# xboxhdmi.net
KiCad netlist of a schematic drawn in EAGLE
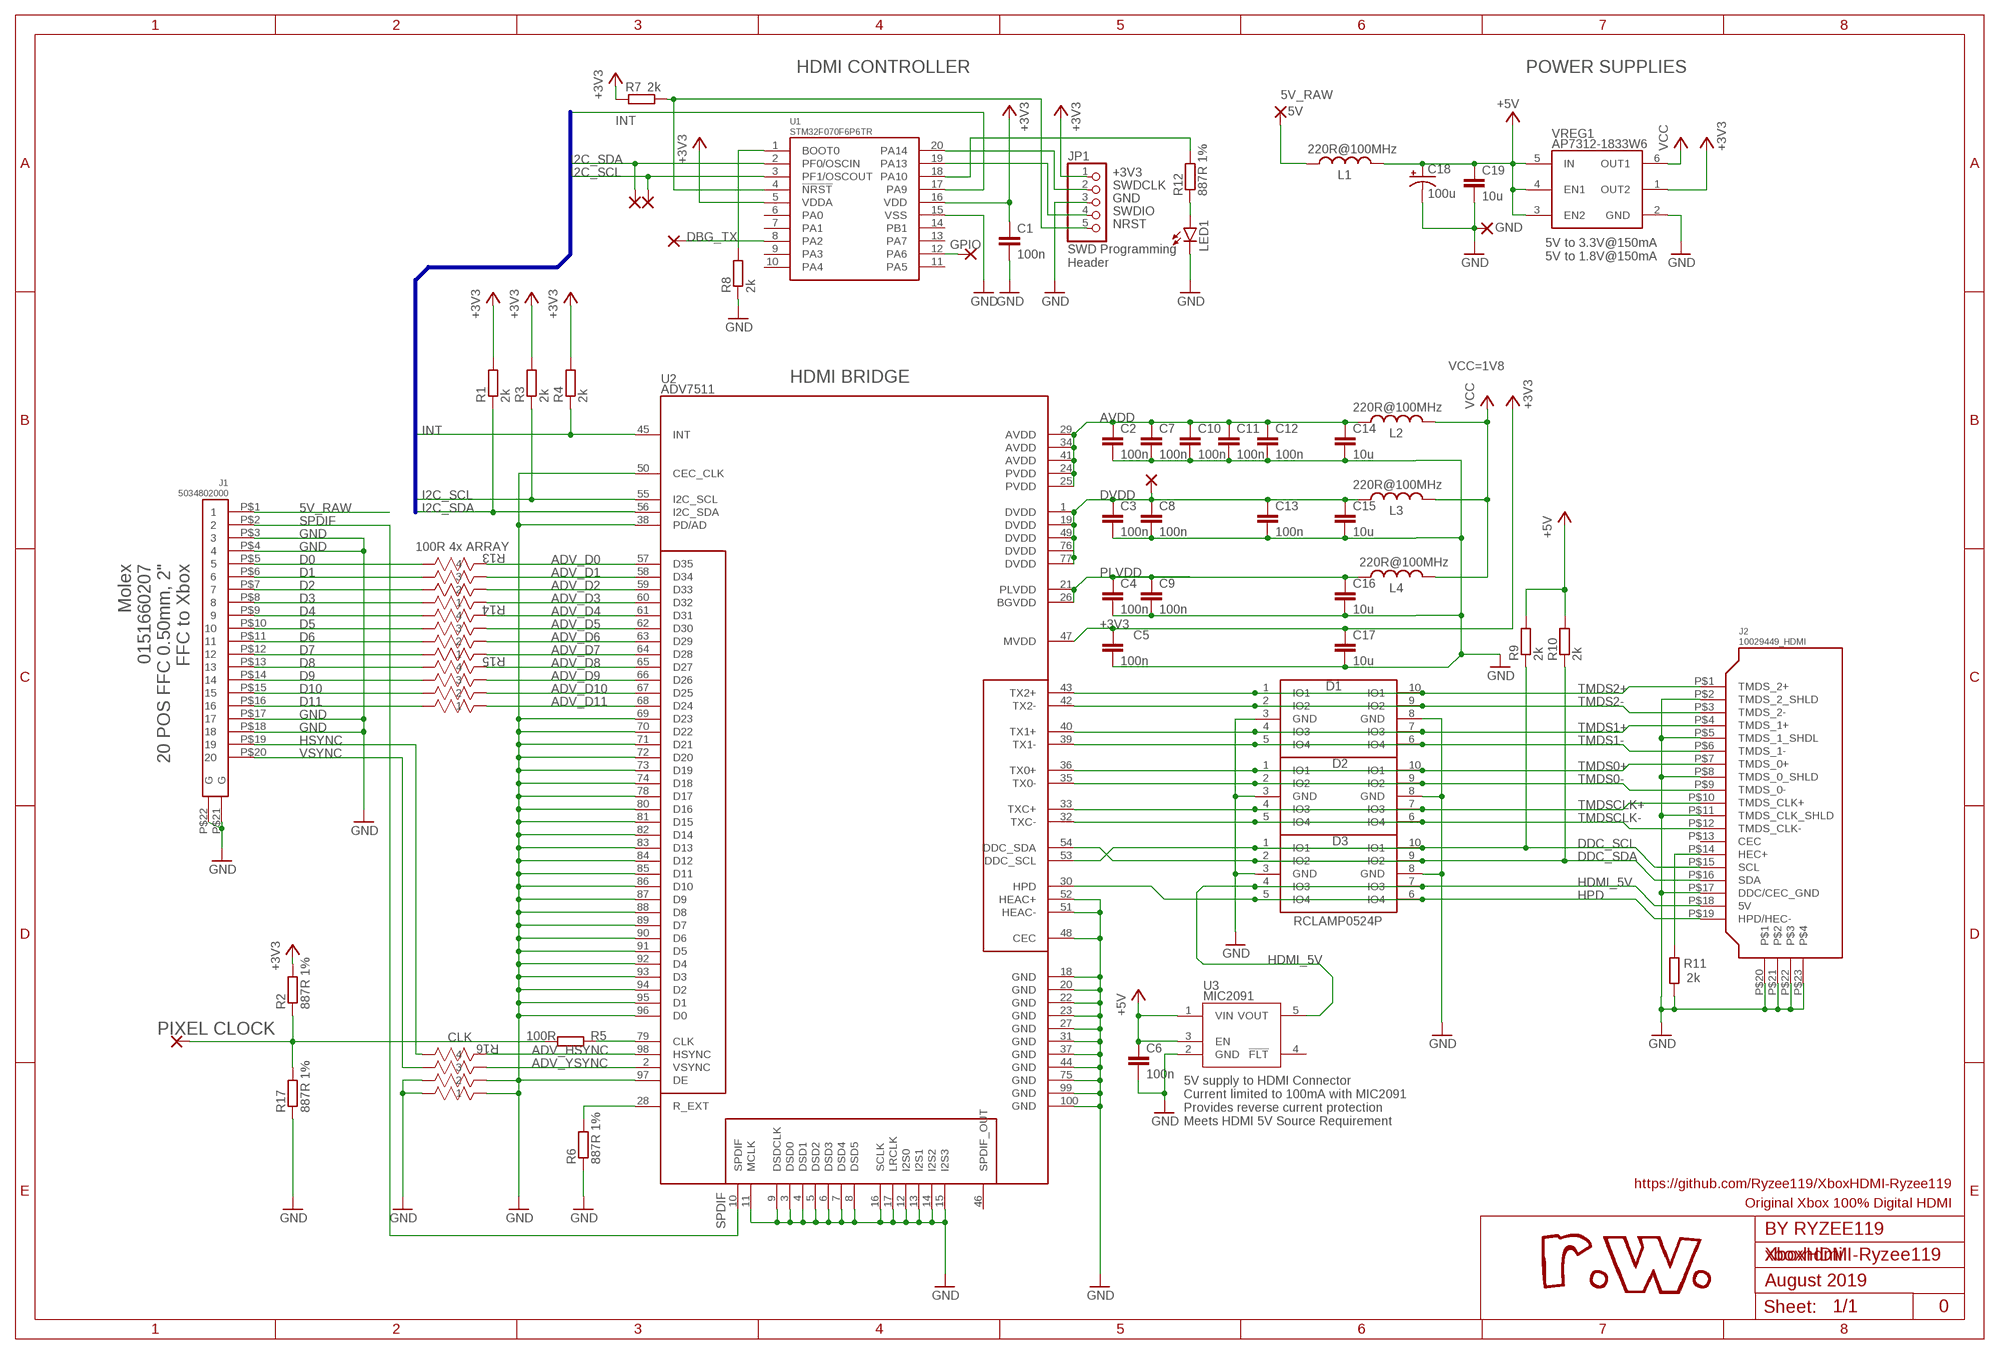
[diagram p0: schematic, sheet 1]

(export (version "E")
  (design (tool "Eeschema 10.0.6"))
  (components
    (comp (ref "1V8")
      (value "SMD2")
      (footprint "eagle-import:SMD1,27-2,54")
      (libsource (lib "eagle-import") (part "SMD2"))
    )
    (comp (ref "5V")
      (value "SMD2")
      (footprint "eagle-import:SMD1,27-2,54")
      (libsource (lib "eagle-import") (part "SMD2"))
    )
    (comp (ref "C1")
      (value "100n")
      (footprint "eagle-import:C0603")
      (libsource (lib "eagle-import") (part "C-EUC0603"))
    )
    (comp (ref "C2")
      (value "100n")
      (footprint "eagle-import:C0603")
      (libsource (lib "eagle-import") (part "C-EUC0603"))
    )
    (comp (ref "C3")
      (value "100n")
      (footprint "eagle-import:C0603")
      (libsource (lib "eagle-import") (part "C-EUC0603"))
    )
    (comp (ref "C4")
      (value "100n")
      (footprint "eagle-import:C0603")
      (libsource (lib "eagle-import") (part "C-EUC0603"))
    )
    (comp (ref "C5")
      (value "100n")
      (footprint "eagle-import:C0603")
      (libsource (lib "eagle-import") (part "C-EUC0603"))
    )
    (comp (ref "C6")
      (value "100n")
      (footprint "eagle-import:C0603")
      (libsource (lib "eagle-import") (part "C-EUC0603"))
    )
    (comp (ref "C7")
      (value "100n")
      (footprint "eagle-import:C0603")
      (libsource (lib "eagle-import") (part "C-EUC0603"))
    )
    (comp (ref "C8")
      (value "100n")
      (footprint "eagle-import:C0603")
      (libsource (lib "eagle-import") (part "C-EUC0603"))
    )
    (comp (ref "C9")
      (value "100n")
      (footprint "eagle-import:C0603")
      (libsource (lib "eagle-import") (part "C-EUC0603"))
    )
    (comp (ref "C10")
      (value "100n")
      (footprint "eagle-import:C0603")
      (libsource (lib "eagle-import") (part "C-EUC0603"))
    )
    (comp (ref "C11")
      (value "100n")
      (footprint "eagle-import:C0603")
      (libsource (lib "eagle-import") (part "C-EUC0603"))
    )
    (comp (ref "C12")
      (value "100n")
      (footprint "eagle-import:C0603")
      (libsource (lib "eagle-import") (part "C-EUC0603"))
    )
    (comp (ref "C13")
      (value "100n")
      (footprint "eagle-import:C0603")
      (libsource (lib "eagle-import") (part "C-EUC0603"))
    )
    (comp (ref "C14")
      (value "10u")
      (footprint "eagle-import:C1206")
      (libsource (lib "eagle-import") (part "C-EUC1206"))
    )
    (comp (ref "C15")
      (value "10u")
      (footprint "eagle-import:C1206")
      (libsource (lib "eagle-import") (part "C-EUC1206"))
    )
    (comp (ref "C16")
      (value "10u")
      (footprint "eagle-import:C1206")
      (libsource (lib "eagle-import") (part "C-EUC1206"))
    )
    (comp (ref "C17")
      (value "10u")
      (footprint "eagle-import:C1206")
      (libsource (lib "eagle-import") (part "C-EUC1206"))
    )
    (comp (ref "C18")
      (value "100u")
      (footprint "eagle-import:153CLV-0505")
      (libsource (lib "eagle-import") (part "CPOL-US153CLV-0505"))
    )
    (comp (ref "C19")
      (value "10u")
      (footprint "eagle-import:C1206")
      (libsource (lib "eagle-import") (part "C-EUC1206"))
    )
    (comp (ref "CLK")
      (value "SMD2")
      (footprint "eagle-import:SMD1,27-2,54")
      (libsource (lib "eagle-import") (part "SMD2"))
    )
    (comp (ref "D1")
      (value "RCLAMP0524P")
      (footprint "eagle-import:DIOCAF50P250X100X65-10")
      (libsource (lib "eagle-import") (part "RCLAMP0524P"))
    )
    (comp (ref "D2")
      (value "RCLAMP0524P")
      (footprint "eagle-import:DIOCAF50P250X100X65-10")
      (libsource (lib "eagle-import") (part "RCLAMP0524P"))
    )
    (comp (ref "D3")
      (value "RCLAMP0524P")
      (footprint "eagle-import:DIOCAF50P250X100X65-10")
      (libsource (lib "eagle-import") (part "RCLAMP0524P"))
    )
    (comp (ref "GND")
      (value "SMD2")
      (footprint "eagle-import:SMD1,27-2,54")
      (libsource (lib "eagle-import") (part "SMD2"))
    )
    (comp (ref "J1")
      (value "5034802000")
      (footprint "eagle-import:5034802000")
      (libsource (lib "eagle-import") (part "5034802000"))
    )
    (comp (ref "J2")
      (value "10029449_HDMI")
      (footprint "eagle-import:HDMI_10029449")
      (libsource (lib "eagle-import") (part "10029449_HDMI"))
    )
    (comp (ref "JP1")
      (value "PINHD-1X5")
      (footprint "eagle-import:1X05")
      (libsource (lib "eagle-import") (part "PINHD-1X5"))
    )
    (comp (ref "L1")
      (value "220R@100MHz")
      (footprint "eagle-import:C0603")
      (libsource (lib "eagle-import") (part "INDUCTOR-0603"))
    )
    (comp (ref "L2")
      (value "220R@100MHz")
      (footprint "eagle-import:C0603")
      (libsource (lib "eagle-import") (part "INDUCTOR-0603"))
    )
    (comp (ref "L3")
      (value "220R@100MHz")
      (footprint "eagle-import:C0603")
      (libsource (lib "eagle-import") (part "INDUCTOR-0603"))
    )
    (comp (ref "L4")
      (value "220R@100MHz")
      (footprint "eagle-import:C0603")
      (libsource (lib "eagle-import") (part "INDUCTOR-0603"))
    )
    (comp (ref "LED1")
      (value "LEDCHIP-LED0603")
      (footprint "eagle-import:CHIP-LED0603")
      (libsource (lib "eagle-import") (part "LEDCHIP-LED0603"))
    )
    (comp (ref "PAD3")
      (value "SMD2")
      (footprint "eagle-import:SMD1,27-2,54")
      (libsource (lib "eagle-import") (part "SMD2"))
    )
    (comp (ref "PAD4")
      (value "SMD2")
      (footprint "eagle-import:SMD1,27-2,54")
      (libsource (lib "eagle-import") (part "SMD2"))
    )
    (comp (ref "PAD5")
      (value "SMD2")
      (footprint "eagle-import:SMD1,27-2,54")
      (libsource (lib "eagle-import") (part "SMD2"))
    )
    (comp (ref "R1")
      (value "2k")
      (footprint "eagle-import:R0603")
      (libsource (lib "eagle-import") (part "R-EU_R0603"))
    )
    (comp (ref "R2")
      (value "887R 1%")
      (footprint "eagle-import:R0603")
      (libsource (lib "eagle-import") (part "R-EU_R0603"))
    )
    (comp (ref "R3")
      (value "2k")
      (footprint "eagle-import:R0603")
      (libsource (lib "eagle-import") (part "R-EU_R0603"))
    )
    (comp (ref "R4")
      (value "2k")
      (footprint "eagle-import:R0603")
      (libsource (lib "eagle-import") (part "R-EU_R0603"))
    )
    (comp (ref "R5")
      (value "100R")
      (footprint "eagle-import:R0603")
      (libsource (lib "eagle-import") (part "R-EU_R0603"))
    )
    (comp (ref "R6")
      (value "887R 1%")
      (footprint "eagle-import:R0603")
      (libsource (lib "eagle-import") (part "R-EU_R0603"))
    )
    (comp (ref "R7")
      (value "2k")
      (footprint "eagle-import:R0603")
      (libsource (lib "eagle-import") (part "R-EU_R0603"))
    )
    (comp (ref "R8")
      (value "2k")
      (footprint "eagle-import:R0603")
      (libsource (lib "eagle-import") (part "R-EU_R0603"))
    )
    (comp (ref "R9")
      (value "2k")
      (footprint "eagle-import:R0603")
      (libsource (lib "eagle-import") (part "R-EU_R0603"))
    )
    (comp (ref "R10")
      (value "2k")
      (footprint "eagle-import:R0603")
      (libsource (lib "eagle-import") (part "R-EU_R0603"))
    )
    (comp (ref "R11")
      (value "2k")
      (footprint "eagle-import:R0603")
      (libsource (lib "eagle-import") (part "R-EU_R0603"))
    )
    (comp (ref "R12")
      (value "887R 1%")
      (footprint "eagle-import:R0603")
      (libsource (lib "eagle-import") (part "R-EU_R0603"))
    )
    (comp (ref "R13")
      (value "YC124-JR-0733RL")
      (footprint "eagle-import:YAG_YC124")
      (fields (field (name "MANUFACTURER_PART_NUMBER") "YC124JR0733RL"))
      (libsource (lib "eagle-import") (part "YC124-JR-0733RL"))
    )
    (comp (ref "R14")
      (value "YC124-JR-0733RL")
      (footprint "eagle-import:YAG_YC124")
      (fields (field (name "MANUFACTURER_PART_NUMBER") "YC124JR0733RL"))
      (libsource (lib "eagle-import") (part "YC124-JR-0733RL"))
    )
    (comp (ref "R15")
      (value "YC124-JR-0733RL")
      (footprint "eagle-import:YAG_YC124")
      (fields (field (name "MANUFACTURER_PART_NUMBER") "YC124JR0733RL"))
      (libsource (lib "eagle-import") (part "YC124-JR-0733RL"))
    )
    (comp (ref "R16")
      (value "YC124-JR-0733RL")
      (footprint "eagle-import:YAG_YC124")
      (fields (field (name "MANUFACTURER_PART_NUMBER") "YC124JR0733RL"))
      (libsource (lib "eagle-import") (part "YC124-JR-0733RL"))
    )
    (comp (ref "R17")
      (value "887R 1%")
      (footprint "eagle-import:R0603")
      (libsource (lib "eagle-import") (part "R-EU_R0603"))
    )
    (comp (ref "TX")
      (value "SMD2")
      (footprint "eagle-import:SMD1,27-2,54")
      (libsource (lib "eagle-import") (part "SMD2"))
    )
    (comp (ref "U1")
      (value "STM32F070F6P6TR")
      (footprint "eagle-import:TSSOP20")
      (libsource (lib "eagle-import") (part "STM32F070F6P6TR"))
    )
    (comp (ref "U2")
      (value "ADV7511")
      (footprint "eagle-import:LQFP100")
      (libsource (lib "eagle-import") (part "ADV7511"))
    )
    (comp (ref "U3")
      (value "MIC2091")
      (footprint "eagle-import:SOT23-5")
      (libsource (lib "eagle-import") (part "MIC2091"))
    )
    (comp (ref "VREG1")
      (value "AP7312-1833W6")
      (footprint "eagle-import:SOT23-6")
      (libsource (lib "eagle-import") (part "AP7312-1833W6"))
    )
  )
  (nets
    (net (code "1") (name "+3V3") (class "Default")
      (node (ref "C1") (pin "1") (pinfunction "1_1") (pintype "passive"))
      (node (ref "C17") (pin "1") (pinfunction "1_1") (pintype "passive"))
      (node (ref "C5") (pin "1") (pinfunction "1_1") (pintype "passive"))
      (node (ref "JP1") (pin "1") (pinfunction "1_1") (pintype "passive"))
      (node (ref "R1") (pin "2") (pinfunction "2_2") (pintype "passive"))
      (node (ref "R2") (pin "2") (pinfunction "2_2") (pintype "passive"))
      (node (ref "R3") (pin "2") (pinfunction "2_2") (pintype "passive"))
      (node (ref "R4") (pin "2") (pinfunction "2_2") (pintype "passive"))
      (node (ref "R7") (pin "2") (pinfunction "2_2") (pintype "passive"))
      (node (ref "U1") (pin "16") (pinfunction "VDD_16") (pintype "bidirectional"))
      (node (ref "U1") (pin "5") (pinfunction "VDDA_5") (pintype "bidirectional"))
      (node (ref "U2") (pin "47") (pinfunction "MVDD_47") (pintype "bidirectional"))
      (node (ref "VREG1") (pin "1") (pinfunction "OUT2_1") (pintype "bidirectional"))
    )
    (net (code "2") (name "+5V") (class "Default")
      (node (ref "C18") (pin "+") (pinfunction "+_+") (pintype "passive"))
      (node (ref "C19") (pin "1") (pinfunction "1_1") (pintype "passive"))
      (node (ref "C6") (pin "1") (pinfunction "1_1") (pintype "passive"))
      (node (ref "L1") (pin "2") (pinfunction "2_2") (pintype "passive"))
      (node (ref "R10") (pin "2") (pinfunction "2_2") (pintype "passive"))
      (node (ref "R9") (pin "2") (pinfunction "2_2") (pintype "passive"))
      (node (ref "U3") (pin "1") (pinfunction "VIN_1") (pintype "bidirectional"))
      (node (ref "U3") (pin "3") (pinfunction "EN_3") (pintype "bidirectional"))
      (node (ref "VREG1") (pin "3") (pinfunction "EN2_3") (pintype "bidirectional"))
      (node (ref "VREG1") (pin "4") (pinfunction "EN1_4") (pintype "bidirectional"))
      (node (ref "VREG1") (pin "5") (pinfunction "IN_5") (pintype "bidirectional"))
    )
    (net (code "3") (name "/5V_RAW") (class "Default")
      (node (ref "5V") (pin "1") (pinfunction "P_1") (pintype "passive"))
      (node (ref "J1") (pin "P$1") (pinfunction "1_P$1") (pintype "bidirectional"))
      (node (ref "L1") (pin "1") (pinfunction "1_1") (pintype "passive"))
    )
    (net (code "4") (name "/ADV_D0") (class "Default")
      (node (ref "R13") (pin "4") (pinfunction "4_4") (pintype "passive"))
      (node (ref "U2") (pin "57") (pinfunction "D35_57") (pintype "bidirectional"))
    )
    (net (code "5") (name "/ADV_D1") (class "Default")
      (node (ref "R13") (pin "3") (pinfunction "3_3") (pintype "passive"))
      (node (ref "U2") (pin "58") (pinfunction "D34_58") (pintype "bidirectional"))
    )
    (net (code "6") (name "/ADV_D2") (class "Default")
      (node (ref "R13") (pin "2") (pinfunction "2_2") (pintype "passive"))
      (node (ref "U2") (pin "59") (pinfunction "D33_59") (pintype "bidirectional"))
    )
    (net (code "7") (name "/ADV_D3") (class "Default")
      (node (ref "R13") (pin "1") (pinfunction "1_1") (pintype "passive"))
      (node (ref "U2") (pin "60") (pinfunction "D32_60") (pintype "bidirectional"))
    )
    (net (code "8") (name "/ADV_D4") (class "Default")
      (node (ref "R14") (pin "4") (pinfunction "4_4") (pintype "passive"))
      (node (ref "U2") (pin "61") (pinfunction "D31_61") (pintype "bidirectional"))
    )
    (net (code "9") (name "/ADV_D5") (class "Default")
      (node (ref "R14") (pin "3") (pinfunction "3_3") (pintype "passive"))
      (node (ref "U2") (pin "62") (pinfunction "D30_62") (pintype "bidirectional"))
    )
    (net (code "10") (name "/ADV_D6") (class "Default")
      (node (ref "R14") (pin "2") (pinfunction "2_2") (pintype "passive"))
      (node (ref "U2") (pin "63") (pinfunction "D29_63") (pintype "bidirectional"))
    )
    (net (code "11") (name "/ADV_D7") (class "Default")
      (node (ref "R14") (pin "1") (pinfunction "1_1") (pintype "passive"))
      (node (ref "U2") (pin "64") (pinfunction "D28_64") (pintype "bidirectional"))
    )
    (net (code "12") (name "/ADV_D8") (class "Default")
      (node (ref "R15") (pin "4") (pinfunction "4_4") (pintype "passive"))
      (node (ref "U2") (pin "65") (pinfunction "D27_65") (pintype "bidirectional"))
    )
    (net (code "13") (name "/ADV_D9") (class "Default")
      (node (ref "R15") (pin "3") (pinfunction "3_3") (pintype "passive"))
      (node (ref "U2") (pin "66") (pinfunction "D26_66") (pintype "bidirectional"))
    )
    (net (code "14") (name "/ADV_D10") (class "Default")
      (node (ref "R15") (pin "2") (pinfunction "2_2") (pintype "passive"))
      (node (ref "U2") (pin "67") (pinfunction "D25_67") (pintype "bidirectional"))
    )
    (net (code "15") (name "/ADV_D11") (class "Default")
      (node (ref "R15") (pin "1") (pinfunction "1_1") (pintype "passive"))
      (node (ref "U2") (pin "68") (pinfunction "D24_68") (pintype "bidirectional"))
    )
    (net (code "16") (name "/ADV_HSYNC") (class "Default")
      (node (ref "R16") (pin "4") (pinfunction "4_4") (pintype "passive"))
      (node (ref "U2") (pin "98") (pinfunction "HSYNC_98") (pintype "bidirectional"))
    )
    (net (code "17") (name "/ADV_YSYNC") (class "Default")
      (node (ref "R16") (pin "3") (pinfunction "3_3") (pintype "passive"))
      (node (ref "U2") (pin "2") (pinfunction "VSYNC_2") (pintype "bidirectional"))
    )
    (net (code "18") (name "/AVDD") (class "Default")
      (node (ref "C10") (pin "1") (pinfunction "1_1") (pintype "passive"))
      (node (ref "C11") (pin "1") (pinfunction "1_1") (pintype "passive"))
      (node (ref "C12") (pin "1") (pinfunction "1_1") (pintype "passive"))
      (node (ref "C14") (pin "1") (pinfunction "1_1") (pintype "passive"))
      (node (ref "C2") (pin "1") (pinfunction "1_1") (pintype "passive"))
      (node (ref "C7") (pin "1") (pinfunction "1_1") (pintype "passive"))
      (node (ref "L2") (pin "1") (pinfunction "1_1") (pintype "passive"))
      (node (ref "U2") (pin "24") (pinfunction "PVDD_24") (pintype "bidirectional"))
      (node (ref "U2") (pin "25") (pinfunction "PVDD_25") (pintype "bidirectional"))
      (node (ref "U2") (pin "29") (pinfunction "AVDD_29") (pintype "bidirectional"))
      (node (ref "U2") (pin "34") (pinfunction "AVDD_34") (pintype "bidirectional"))
      (node (ref "U2") (pin "41") (pinfunction "AVDD_41") (pintype "bidirectional"))
    )
    (net (code "19") (name "/CLK") (class "Default")
      (node (ref "CLK") (pin "1") (pinfunction "P_1") (pintype "passive"))
      (node (ref "R17") (pin "2") (pinfunction "2_2") (pintype "passive"))
      (node (ref "R2") (pin "1") (pinfunction "1_1") (pintype "passive"))
      (node (ref "R5") (pin "2") (pinfunction "2_2") (pintype "passive"))
    )
    (net (code "20") (name "/D0") (class "Default")
      (node (ref "J1") (pin "P$5") (pinfunction "5_P$5") (pintype "bidirectional"))
      (node (ref "R13") (pin "5") (pinfunction "5_5") (pintype "passive"))
    )
    (net (code "21") (name "/D1") (class "Default")
      (node (ref "J1") (pin "P$6") (pinfunction "6_P$6") (pintype "bidirectional"))
      (node (ref "R13") (pin "6") (pinfunction "6_6") (pintype "passive"))
    )
    (net (code "22") (name "/D2") (class "Default")
      (node (ref "J1") (pin "P$7") (pinfunction "7_P$7") (pintype "bidirectional"))
      (node (ref "R13") (pin "7") (pinfunction "7_7") (pintype "passive"))
    )
    (net (code "23") (name "/D3") (class "Default")
      (node (ref "J1") (pin "P$8") (pinfunction "8_P$8") (pintype "bidirectional"))
      (node (ref "R13") (pin "8") (pinfunction "8_8") (pintype "passive"))
    )
    (net (code "24") (name "/D4") (class "Default")
      (node (ref "J1") (pin "P$9") (pinfunction "9_P$9") (pintype "bidirectional"))
      (node (ref "R14") (pin "5") (pinfunction "5_5") (pintype "passive"))
    )
    (net (code "25") (name "/D5") (class "Default")
      (node (ref "J1") (pin "P$10") (pinfunction "10_P$10") (pintype "bidirectional"))
      (node (ref "R14") (pin "6") (pinfunction "6_6") (pintype "passive"))
    )
    (net (code "26") (name "/D6") (class "Default")
      (node (ref "J1") (pin "P$11") (pinfunction "11_P$11") (pintype "bidirectional"))
      (node (ref "R14") (pin "7") (pinfunction "7_7") (pintype "passive"))
    )
    (net (code "27") (name "/D7") (class "Default")
      (node (ref "J1") (pin "P$12") (pinfunction "12_P$12") (pintype "bidirectional"))
      (node (ref "R14") (pin "8") (pinfunction "8_8") (pintype "passive"))
    )
    (net (code "28") (name "/D8") (class "Default")
      (node (ref "J1") (pin "P$13") (pinfunction "13_P$13") (pintype "bidirectional"))
      (node (ref "R15") (pin "5") (pinfunction "5_5") (pintype "passive"))
    )
    (net (code "29") (name "/D9") (class "Default")
      (node (ref "J1") (pin "P$14") (pinfunction "14_P$14") (pintype "bidirectional"))
      (node (ref "R15") (pin "6") (pinfunction "6_6") (pintype "passive"))
    )
    (net (code "30") (name "/D10") (class "Default")
      (node (ref "J1") (pin "P$15") (pinfunction "15_P$15") (pintype "bidirectional"))
      (node (ref "R15") (pin "7") (pinfunction "7_7") (pintype "passive"))
    )
    (net (code "31") (name "/D11") (class "Default")
      (node (ref "J1") (pin "P$16") (pinfunction "16_P$16") (pintype "bidirectional"))
      (node (ref "R15") (pin "8") (pinfunction "8_8") (pintype "passive"))
    )
    (net (code "32") (name "/DBG_TX") (class "Default")
      (node (ref "TX") (pin "1") (pinfunction "P_1") (pintype "passive"))
      (node (ref "U1") (pin "8") (pinfunction "PA2_8") (pintype "bidirectional"))
    )
    (net (code "33") (name "/DDC_SCL") (class "Default")
      (node (ref "D3") (pin "1") (pinfunction "IO1_1") (pintype "bidirectional"))
      (node (ref "D3") (pin "10") (pinfunction "IO1_10") (pintype "bidirectional"))
      (node (ref "J2") (pin "P$15") (pinfunction "SCL_P$15") (pintype "bidirectional"))
      (node (ref "R9") (pin "1") (pinfunction "1_1") (pintype "passive"))
      (node (ref "U2") (pin "53") (pinfunction "DDC_SCL_53") (pintype "bidirectional"))
    )
    (net (code "34") (name "/DDC_SDA") (class "Default")
      (node (ref "D3") (pin "2") (pinfunction "IO2_2") (pintype "bidirectional"))
      (node (ref "D3") (pin "9") (pinfunction "IO2_9") (pintype "bidirectional"))
      (node (ref "J2") (pin "P$16") (pinfunction "SDA_P$16") (pintype "bidirectional"))
      (node (ref "R10") (pin "1") (pinfunction "1_1") (pintype "passive"))
      (node (ref "U2") (pin "54") (pinfunction "DDC_SDA_54") (pintype "bidirectional"))
    )
    (net (code "35") (name "/DVDD") (class "Default")
      (node (ref "1V8") (pin "1") (pinfunction "P_1") (pintype "passive"))
      (node (ref "C13") (pin "1") (pinfunction "1_1") (pintype "passive"))
      (node (ref "C15") (pin "1") (pinfunction "1_1") (pintype "passive"))
      (node (ref "C3") (pin "1") (pinfunction "1_1") (pintype "passive"))
      (node (ref "C8") (pin "1") (pinfunction "1_1") (pintype "passive"))
      (node (ref "L3") (pin "1") (pinfunction "1_1") (pintype "passive"))
      (node (ref "U2") (pin "1") (pinfunction "DVDD_1") (pintype "bidirectional"))
      (node (ref "U2") (pin "19") (pinfunction "DVDD_19") (pintype "bidirectional"))
      (node (ref "U2") (pin "49") (pinfunction "DVDD_49") (pintype "bidirectional"))
      (node (ref "U2") (pin "76") (pinfunction "DVDD_76") (pintype "bidirectional"))
      (node (ref "U2") (pin "77") (pinfunction "DVDD_77") (pintype "bidirectional"))
    )
    (net (code "36") (name "/GPIO") (class "Default")
      (node (ref "PAD5") (pin "1") (pinfunction "P_1") (pintype "passive"))
      (node (ref "U1") (pin "12") (pinfunction "PA6_12") (pintype "bidirectional"))
    )
    (net (code "37") (name "/HDMI_5V") (class "Default")
      (node (ref "D3") (pin "4") (pinfunction "IO3_4") (pintype "bidirectional"))
      (node (ref "D3") (pin "7") (pinfunction "IO3_7") (pintype "bidirectional"))
      (node (ref "J2") (pin "P$18") (pinfunction "5V_P$18") (pintype "bidirectional"))
      (node (ref "U3") (pin "5") (pinfunction "VOUT_5") (pintype "bidirectional"))
    )
    (net (code "38") (name "/HPD") (class "Default")
      (node (ref "D3") (pin "5") (pinfunction "IO4_5") (pintype "bidirectional"))
      (node (ref "D3") (pin "6") (pinfunction "IO4_6") (pintype "bidirectional"))
      (node (ref "J2") (pin "P$19") (pinfunction "HPD/HEC-_P$19") (pintype "bidirectional"))
      (node (ref "U2") (pin "30") (pinfunction "HPD_30") (pintype "bidirectional"))
    )
    (net (code "39") (name "/HSYNC") (class "Default")
      (node (ref "J1") (pin "P$19") (pinfunction "19_P$19") (pintype "bidirectional"))
      (node (ref "R16") (pin "5") (pinfunction "5_5") (pintype "passive"))
    )
    (net (code "40") (name "/I2C_SCL") (class "Default")
      (node (ref "PAD4") (pin "1") (pinfunction "P_1") (pintype "passive"))
      (node (ref "R3") (pin "1") (pinfunction "1_1") (pintype "passive"))
      (node (ref "U1") (pin "3") (pinfunction "PF1/OSCOUT_3") (pintype "bidirectional"))
      (node (ref "U2") (pin "55") (pinfunction "I2C_SCL_55") (pintype "bidirectional"))
    )
    (net (code "41") (name "/I2C_SDA") (class "Default")
      (node (ref "PAD3") (pin "1") (pinfunction "P_1") (pintype "passive"))
      (node (ref "R1") (pin "1") (pinfunction "1_1") (pintype "passive"))
      (node (ref "U1") (pin "2") (pinfunction "PF0/OSCIN_2") (pintype "bidirectional"))
      (node (ref "U2") (pin "56") (pinfunction "I2C_SDA_56") (pintype "bidirectional"))
    )
    (net (code "42") (name "/INT") (class "Default")
      (node (ref "R4") (pin "1") (pinfunction "1_1") (pintype "passive"))
      (node (ref "U1") (pin "17") (pinfunction "PA9_17") (pintype "bidirectional"))
      (node (ref "U2") (pin "45") (pinfunction "INT_45") (pintype "bidirectional"))
    )
    (net (code "43") (name "/NRST") (class "Default")
      (node (ref "JP1") (pin "5") (pinfunction "5_5") (pintype "passive"))
      (node (ref "R7") (pin "1") (pinfunction "1_1") (pintype "passive"))
      (node (ref "U1") (pin "4") (pinfunction "~{NRST}_4") (pintype "bidirectional"))
    )
    (net (code "44") (name "/PLVDD") (class "Default")
      (node (ref "C16") (pin "1") (pinfunction "1_1") (pintype "passive"))
      (node (ref "C4") (pin "1") (pinfunction "1_1") (pintype "passive"))
      (node (ref "C9") (pin "1") (pinfunction "1_1") (pintype "passive"))
      (node (ref "L4") (pin "1") (pinfunction "1_1") (pintype "passive"))
      (node (ref "U2") (pin "21") (pinfunction "PLVDD_21") (pintype "bidirectional"))
      (node (ref "U2") (pin "26") (pinfunction "BGVDD_26") (pintype "bidirectional"))
    )
    (net (code "45") (name "/SPDIF") (class "Default")
      (node (ref "J1") (pin "P$2") (pinfunction "2_P$2") (pintype "bidirectional"))
      (node (ref "U2") (pin "10") (pinfunction "SPDIF_10") (pintype "bidirectional"))
    )
    (net (code "46") (name "/SWDCLK") (class "Default")
      (node (ref "JP1") (pin "2") (pinfunction "2_2") (pintype "passive"))
      (node (ref "U1") (pin "20") (pinfunction "PA14_20") (pintype "bidirectional"))
    )
    (net (code "47") (name "/SWDIO") (class "Default")
      (node (ref "JP1") (pin "4") (pinfunction "4_4") (pintype "passive"))
      (node (ref "U1") (pin "19") (pinfunction "PA13_19") (pintype "bidirectional"))
    )
    (net (code "48") (name "/TMDS0+") (class "Default")
      (node (ref "D2") (pin "1") (pinfunction "IO1_1") (pintype "bidirectional"))
      (node (ref "D2") (pin "10") (pinfunction "IO1_10") (pintype "bidirectional"))
      (node (ref "J2") (pin "P$7") (pinfunction "TMDS_0+_P$7") (pintype "bidirectional"))
      (node (ref "U2") (pin "36") (pinfunction "TX0+_36") (pintype "bidirectional"))
    )
    (net (code "49") (name "/TMDS0-") (class "Default")
      (node (ref "D2") (pin "2") (pinfunction "IO2_2") (pintype "bidirectional"))
      (node (ref "D2") (pin "9") (pinfunction "IO2_9") (pintype "bidirectional"))
      (node (ref "J2") (pin "P$9") (pinfunction "TMDS_0-_P$9") (pintype "bidirectional"))
      (node (ref "U2") (pin "35") (pinfunction "TX0-_35") (pintype "bidirectional"))
    )
    (net (code "50") (name "/TMDS1+") (class "Default")
      (node (ref "D1") (pin "4") (pinfunction "IO3_4") (pintype "bidirectional"))
      (node (ref "D1") (pin "7") (pinfunction "IO3_7") (pintype "bidirectional"))
      (node (ref "J2") (pin "P$4") (pinfunction "TMDS_1+_P$4") (pintype "bidirectional"))
      (node (ref "U2") (pin "40") (pinfunction "TX1+_40") (pintype "bidirectional"))
    )
    (net (code "51") (name "/TMDS1-") (class "Default")
      (node (ref "D1") (pin "5") (pinfunction "IO4_5") (pintype "bidirectional"))
      (node (ref "D1") (pin "6") (pinfunction "IO4_6") (pintype "bidirectional"))
      (node (ref "J2") (pin "P$6") (pinfunction "TMDS_1-_P$6") (pintype "bidirectional"))
      (node (ref "U2") (pin "39") (pinfunction "TX1-_39") (pintype "bidirectional"))
    )
    (net (code "52") (name "/TMDS2+") (class "Default")
      (node (ref "D1") (pin "1") (pinfunction "IO1_1") (pintype "bidirectional"))
      (node (ref "D1") (pin "10") (pinfunction "IO1_10") (pintype "bidirectional"))
      (node (ref "J2") (pin "P$1") (pinfunction "TMDS_2+_P$1") (pintype "bidirectional"))
      (node (ref "U2") (pin "43") (pinfunction "TX2+_43") (pintype "bidirectional"))
    )
    (net (code "53") (name "/TMDS2-") (class "Default")
      (node (ref "D1") (pin "2") (pinfunction "IO2_2") (pintype "bidirectional"))
      (node (ref "D1") (pin "9") (pinfunction "IO2_9") (pintype "bidirectional"))
      (node (ref "J2") (pin "P$3") (pinfunction "TMDS_2-_P$3") (pintype "bidirectional"))
      (node (ref "U2") (pin "42") (pinfunction "TX2-_42") (pintype "bidirectional"))
    )
    (net (code "54") (name "/TMDSCLK+") (class "Default")
      (node (ref "D2") (pin "4") (pinfunction "IO3_4") (pintype "bidirectional"))
      (node (ref "D2") (pin "7") (pinfunction "IO3_7") (pintype "bidirectional"))
      (node (ref "J2") (pin "P$10") (pinfunction "TMDS_CLK+_P$10") (pintype "bidirectional"))
      (node (ref "U2") (pin "33") (pinfunction "TXC+_33") (pintype "bidirectional"))
    )
    (net (code "55") (name "/TMDSCLK-") (class "Default")
      (node (ref "D2") (pin "5") (pinfunction "IO4_5") (pintype "bidirectional"))
      (node (ref "D2") (pin "6") (pinfunction "IO4_6") (pintype "bidirectional"))
      (node (ref "J2") (pin "P$12") (pinfunction "TMDS_CLK-_P$12") (pintype "bidirectional"))
      (node (ref "U2") (pin "32") (pinfunction "TXC-_32") (pintype "bidirectional"))
    )
    (net (code "56") (name "/VSYNC") (class "Default")
      (node (ref "J1") (pin "P$20") (pinfunction "20_P$20") (pintype "bidirectional"))
      (node (ref "R16") (pin "6") (pinfunction "6_6") (pintype "passive"))
    )
    (net (code "57") (name "GND") (class "Default")
      (node (ref "C1") (pin "2") (pinfunction "2_2") (pintype "passive"))
      (node (ref "C10") (pin "2") (pinfunction "2_2") (pintype "passive"))
      (node (ref "C11") (pin "2") (pinfunction "2_2") (pintype "passive"))
      (node (ref "C12") (pin "2") (pinfunction "2_2") (pintype "passive"))
      (node (ref "C13") (pin "2") (pinfunction "2_2") (pintype "passive"))
      (node (ref "C14") (pin "2") (pinfunction "2_2") (pintype "passive"))
      (node (ref "C15") (pin "2") (pinfunction "2_2") (pintype "passive"))
      (node (ref "C16") (pin "2") (pinfunction "2_2") (pintype "passive"))
      (node (ref "C17") (pin "2") (pinfunction "2_2") (pintype "passive"))
      (node (ref "C18") (pin "-") (pinfunction "-_-") (pintype "passive"))
      (node (ref "C19") (pin "2") (pinfunction "2_2") (pintype "passive"))
      (node (ref "C2") (pin "2") (pinfunction "2_2") (pintype "passive"))
      (node (ref "C3") (pin "2") (pinfunction "2_2") (pintype "passive"))
      (node (ref "C4") (pin "2") (pinfunction "2_2") (pintype "passive"))
      (node (ref "C5") (pin "2") (pinfunction "2_2") (pintype "passive"))
      (node (ref "C6") (pin "2") (pinfunction "2_2") (pintype "passive"))
      (node (ref "C7") (pin "2") (pinfunction "2_2") (pintype "passive"))
      (node (ref "C8") (pin "2") (pinfunction "2_2") (pintype "passive"))
      (node (ref "C9") (pin "2") (pinfunction "2_2") (pintype "passive"))
      (node (ref "D1") (pin "3") (pinfunction "GND_3") (pintype "bidirectional"))
      (node (ref "D1") (pin "8") (pinfunction "GND_8") (pintype "bidirectional"))
      (node (ref "D2") (pin "3") (pinfunction "GND_3") (pintype "bidirectional"))
      (node (ref "D2") (pin "8") (pinfunction "GND_8") (pintype "bidirectional"))
      (node (ref "D3") (pin "3") (pinfunction "GND_3") (pintype "bidirectional"))
      (node (ref "D3") (pin "8") (pinfunction "GND_8") (pintype "bidirectional"))
      (node (ref "GND") (pin "1") (pinfunction "P_1") (pintype "passive"))
      (node (ref "J1") (pin "P$17") (pinfunction "17_P$17") (pintype "bidirectional"))
      (node (ref "J1") (pin "P$18") (pinfunction "18_P$18") (pintype "bidirectional"))
      (node (ref "J1") (pin "P$21") (pinfunction "G_P$21") (pintype "bidirectional"))
      (node (ref "J1") (pin "P$22") (pinfunction "G_P$22") (pintype "bidirectional"))
      (node (ref "J1") (pin "P$3") (pinfunction "3_P$3") (pintype "bidirectional"))
      (node (ref "J1") (pin "P$4") (pinfunction "4_P$4") (pintype "bidirectional"))
      (node (ref "J2") (pin "P$11") (pinfunction "TMDS_CLK_SHLD_P$11") (pintype "bidirectional"))
      (node (ref "J2") (pin "P$17") (pinfunction "DDC/CEC_GND_P$17") (pintype "bidirectional"))
      (node (ref "J2") (pin "P$2") (pinfunction "TMDS_2_SHLD_P$2") (pintype "bidirectional"))
      (node (ref "J2") (pin "P$20") (pinfunction "P$1_P$20") (pintype "bidirectional"))
      (node (ref "J2") (pin "P$21") (pinfunction "P$2_P$21") (pintype "bidirectional"))
      (node (ref "J2") (pin "P$22") (pinfunction "P$3_P$22") (pintype "bidirectional"))
      (node (ref "J2") (pin "P$23") (pinfunction "P$4_P$23") (pintype "bidirectional"))
      (node (ref "J2") (pin "P$5") (pinfunction "TMDS_1_SHDL_P$5") (pintype "bidirectional"))
      (node (ref "J2") (pin "P$8") (pinfunction "TMDS_0_SHLD_P$8") (pintype "bidirectional"))
      (node (ref "JP1") (pin "3") (pinfunction "3_3") (pintype "passive"))
      (node (ref "LED1") (pin "C") (pinfunction "C_C") (pintype "passive"))
      (node (ref "R11") (pin "1") (pinfunction "1_1") (pintype "passive"))
      (node (ref "R16") (pin "1") (pinfunction "1_1") (pintype "passive"))
      (node (ref "R16") (pin "2") (pinfunction "2_2") (pintype "passive"))
      (node (ref "R16") (pin "7") (pinfunction "7_7") (pintype "passive"))
      (node (ref "R16") (pin "8") (pinfunction "8_8") (pintype "passive"))
      (node (ref "R17") (pin "1") (pinfunction "1_1") (pintype "passive"))
      (node (ref "R6") (pin "1") (pinfunction "1_1") (pintype "passive"))
      (node (ref "R8") (pin "1") (pinfunction "1_1") (pintype "passive"))
      (node (ref "U1") (pin "15") (pinfunction "VSS_15") (pintype "bidirectional"))
      (node (ref "U2") (pin "100") (pinfunction "GND_100") (pintype "bidirectional"))
      (node (ref "U2") (pin "11") (pinfunction "MCLK_11") (pintype "bidirectional"))
      (node (ref "U2") (pin "12") (pinfunction "I2S0_12") (pintype "bidirectional"))
      (node (ref "U2") (pin "13") (pinfunction "I2S1_13") (pintype "bidirectional"))
      (node (ref "U2") (pin "14") (pinfunction "I2S2_14") (pintype "bidirectional"))
      (node (ref "U2") (pin "15") (pinfunction "I2S3_15") (pintype "bidirectional"))
      (node (ref "U2") (pin "16") (pinfunction "SCLK_16") (pintype "bidirectional"))
      (node (ref "U2") (pin "17") (pinfunction "LRCLK_17") (pintype "bidirectional"))
      (node (ref "U2") (pin "18") (pinfunction "GND_18") (pintype "bidirectional"))
      (node (ref "U2") (pin "20") (pinfunction "GND_20") (pintype "bidirectional"))
      (node (ref "U2") (pin "22") (pinfunction "GND_22") (pintype "bidirectional"))
      (node (ref "U2") (pin "23") (pinfunction "GND_23") (pintype "bidirectional"))
      (node (ref "U2") (pin "27") (pinfunction "GND_27") (pintype "bidirectional"))
      (node (ref "U2") (pin "3") (pinfunction "DSD0_3") (pintype "bidirectional"))
      (node (ref "U2") (pin "31") (pinfunction "GND_31") (pintype "bidirectional"))
      (node (ref "U2") (pin "37") (pinfunction "GND_37") (pintype "bidirectional"))
      (node (ref "U2") (pin "38") (pinfunction "PD/AD_38") (pintype "bidirectional"))
      (node (ref "U2") (pin "4") (pinfunction "DSD1_4") (pintype "bidirectional"))
      (node (ref "U2") (pin "44") (pinfunction "GND_44") (pintype "bidirectional"))
      (node (ref "U2") (pin "48") (pinfunction "CEC_48") (pintype "bidirectional"))
      (node (ref "U2") (pin "5") (pinfunction "DSD2_5") (pintype "bidirectional"))
      (node (ref "U2") (pin "50") (pinfunction "CEC_CLK_50") (pintype "bidirectional"))
      (node (ref "U2") (pin "51") (pinfunction "HEAC-_51") (pintype "bidirectional"))
      (node (ref "U2") (pin "52") (pinfunction "HEAC+_52") (pintype "bidirectional"))
      (node (ref "U2") (pin "6") (pinfunction "DSD3_6") (pintype "bidirectional"))
      (node (ref "U2") (pin "69") (pinfunction "D23_69") (pintype "bidirectional"))
      (node (ref "U2") (pin "7") (pinfunction "DSD4_7") (pintype "bidirectional"))
      (node (ref "U2") (pin "70") (pinfunction "D22_70") (pintype "bidirectional"))
      (node (ref "U2") (pin "71") (pinfunction "D21_71") (pintype "bidirectional"))
      (node (ref "U2") (pin "72") (pinfunction "D20_72") (pintype "bidirectional"))
      (node (ref "U2") (pin "73") (pinfunction "D19_73") (pintype "bidirectional"))
      (node (ref "U2") (pin "74") (pinfunction "D18_74") (pintype "bidirectional"))
      (node (ref "U2") (pin "75") (pinfunction "GND_75") (pintype "bidirectional"))
      (node (ref "U2") (pin "78") (pinfunction "D17_78") (pintype "bidirectional"))
      (node (ref "U2") (pin "8") (pinfunction "DSD5_8") (pintype "bidirectional"))
      (node (ref "U2") (pin "80") (pinfunction "D16_80") (pintype "bidirectional"))
      (node (ref "U2") (pin "81") (pinfunction "D15_81") (pintype "bidirectional"))
      (node (ref "U2") (pin "82") (pinfunction "D14_82") (pintype "bidirectional"))
      (node (ref "U2") (pin "83") (pinfunction "D13_83") (pintype "bidirectional"))
      (node (ref "U2") (pin "84") (pinfunction "D12_84") (pintype "bidirectional"))
      (node (ref "U2") (pin "85") (pinfunction "D11_85") (pintype "bidirectional"))
      (node (ref "U2") (pin "86") (pinfunction "D10_86") (pintype "bidirectional"))
      (node (ref "U2") (pin "87") (pinfunction "D9_87") (pintype "bidirectional"))
      (node (ref "U2") (pin "88") (pinfunction "D8_88") (pintype "bidirectional"))
      (node (ref "U2") (pin "89") (pinfunction "D7_89") (pintype "bidirectional"))
      (node (ref "U2") (pin "9") (pinfunction "DSDCLK_9") (pintype "bidirectional"))
      (node (ref "U2") (pin "90") (pinfunction "D6_90") (pintype "bidirectional"))
      (node (ref "U2") (pin "91") (pinfunction "D5_91") (pintype "bidirectional"))
      (node (ref "U2") (pin "92") (pinfunction "D4_92") (pintype "bidirectional"))
      (node (ref "U2") (pin "93") (pinfunction "D3_93") (pintype "bidirectional"))
      (node (ref "U2") (pin "94") (pinfunction "D2_94") (pintype "bidirectional"))
      (node (ref "U2") (pin "95") (pinfunction "D1_95") (pintype "bidirectional"))
      (node (ref "U2") (pin "96") (pinfunction "D0_96") (pintype "bidirectional"))
      (node (ref "U2") (pin "97") (pinfunction "DE_97") (pintype "bidirectional"))
      (node (ref "U2") (pin "99") (pinfunction "GND_99") (pintype "bidirectional"))
      (node (ref "U3") (pin "2") (pinfunction "GND_2") (pintype "bidirectional"))
      (node (ref "VREG1") (pin "2") (pinfunction "GND_2") (pintype "bidirectional"))
    )
    (net (code "58") (name "Net-(J2-HEC+)") (class "Default")
      (node (ref "J2") (pin "P$14") (pinfunction "HEC+_P$14") (pintype "bidirectional"))
      (node (ref "R11") (pin "2") (pinfunction "2_2") (pintype "passive"))
    )
    (net (code "59") (name "Net-(LED1-PadA)") (class "Default")
      (node (ref "LED1") (pin "A") (pinfunction "A_A") (pintype "passive"))
      (node (ref "R12") (pin "1") (pinfunction "1_1") (pintype "passive"))
    )
    (net (code "60") (name "Net-(U1-BOOT0)") (class "Default")
      (node (ref "R8") (pin "2") (pinfunction "2_2") (pintype "passive"))
      (node (ref "U1") (pin "1") (pinfunction "BOOT0_1") (pintype "bidirectional"))
    )
    (net (code "61") (name "Net-(U1-PA10)") (class "Default")
      (node (ref "R12") (pin "2") (pinfunction "2_2") (pintype "passive"))
      (node (ref "U1") (pin "18") (pinfunction "PA10_18") (pintype "bidirectional"))
    )
    (net (code "62") (name "Net-(U2-CLK)") (class "Default")
      (node (ref "R5") (pin "1") (pinfunction "1_1") (pintype "passive"))
      (node (ref "U2") (pin "79") (pinfunction "CLK_79") (pintype "bidirectional"))
    )
    (net (code "63") (name "Net-(U2-R_EXT)") (class "Default")
      (node (ref "R6") (pin "2") (pinfunction "2_2") (pintype "passive"))
      (node (ref "U2") (pin "28") (pinfunction "R_EXT_28") (pintype "bidirectional"))
    )
    (net (code "64") (name "VCC") (class "Default")
      (node (ref "L2") (pin "2") (pinfunction "2_2") (pintype "passive"))
      (node (ref "L3") (pin "2") (pinfunction "2_2") (pintype "passive"))
      (node (ref "L4") (pin "2") (pinfunction "2_2") (pintype "passive"))
      (node (ref "VREG1") (pin "6") (pinfunction "OUT1_6") (pintype "bidirectional"))
    )
    (net (code "65") (name "unconnected-(J2-CEC-PadP$13)") (class "Default")
      (node (ref "J2") (pin "P$13") (pinfunction "CEC_P$13") (pintype "bidirectional"))
    )
    (net (code "66") (name "unconnected-(U1-PA0-Pad6)") (class "Default")
      (node (ref "U1") (pin "6") (pinfunction "PA0_6") (pintype "bidirectional"))
    )
    (net (code "67") (name "unconnected-(U1-PA1-Pad7)") (class "Default")
      (node (ref "U1") (pin "7") (pinfunction "PA1_7") (pintype "bidirectional"))
    )
    (net (code "68") (name "unconnected-(U1-PA3-Pad9)") (class "Default")
      (node (ref "U1") (pin "9") (pinfunction "PA3_9") (pintype "bidirectional"))
    )
    (net (code "69") (name "unconnected-(U1-PA4-Pad10)") (class "Default")
      (node (ref "U1") (pin "10") (pinfunction "PA4_10") (pintype "bidirectional"))
    )
    (net (code "70") (name "unconnected-(U1-PA5-Pad11)") (class "Default")
      (node (ref "U1") (pin "11") (pinfunction "PA5_11") (pintype "bidirectional"))
    )
    (net (code "71") (name "unconnected-(U1-PA7-Pad13)") (class "Default")
      (node (ref "U1") (pin "13") (pinfunction "PA7_13") (pintype "bidirectional"))
    )
    (net (code "72") (name "unconnected-(U1-PB1-Pad14)") (class "Default")
      (node (ref "U1") (pin "14") (pinfunction "PB1_14") (pintype "bidirectional"))
    )
    (net (code "73") (name "unconnected-(U2-SPDIF_OUT-Pad46)") (class "Default")
      (node (ref "U2") (pin "46") (pinfunction "SPDIF_OUT_46") (pintype "bidirectional"))
    )
    (net (code "74") (name "unconnected-(U3-~{FLT}-Pad4)") (class "Default")
      (node (ref "U3") (pin "4") (pinfunction "~{FLT}_4") (pintype "bidirectional"))
    )
  )
)
